# design.net
KiCad netlist of a schematic drawn in EasyEDA Pro
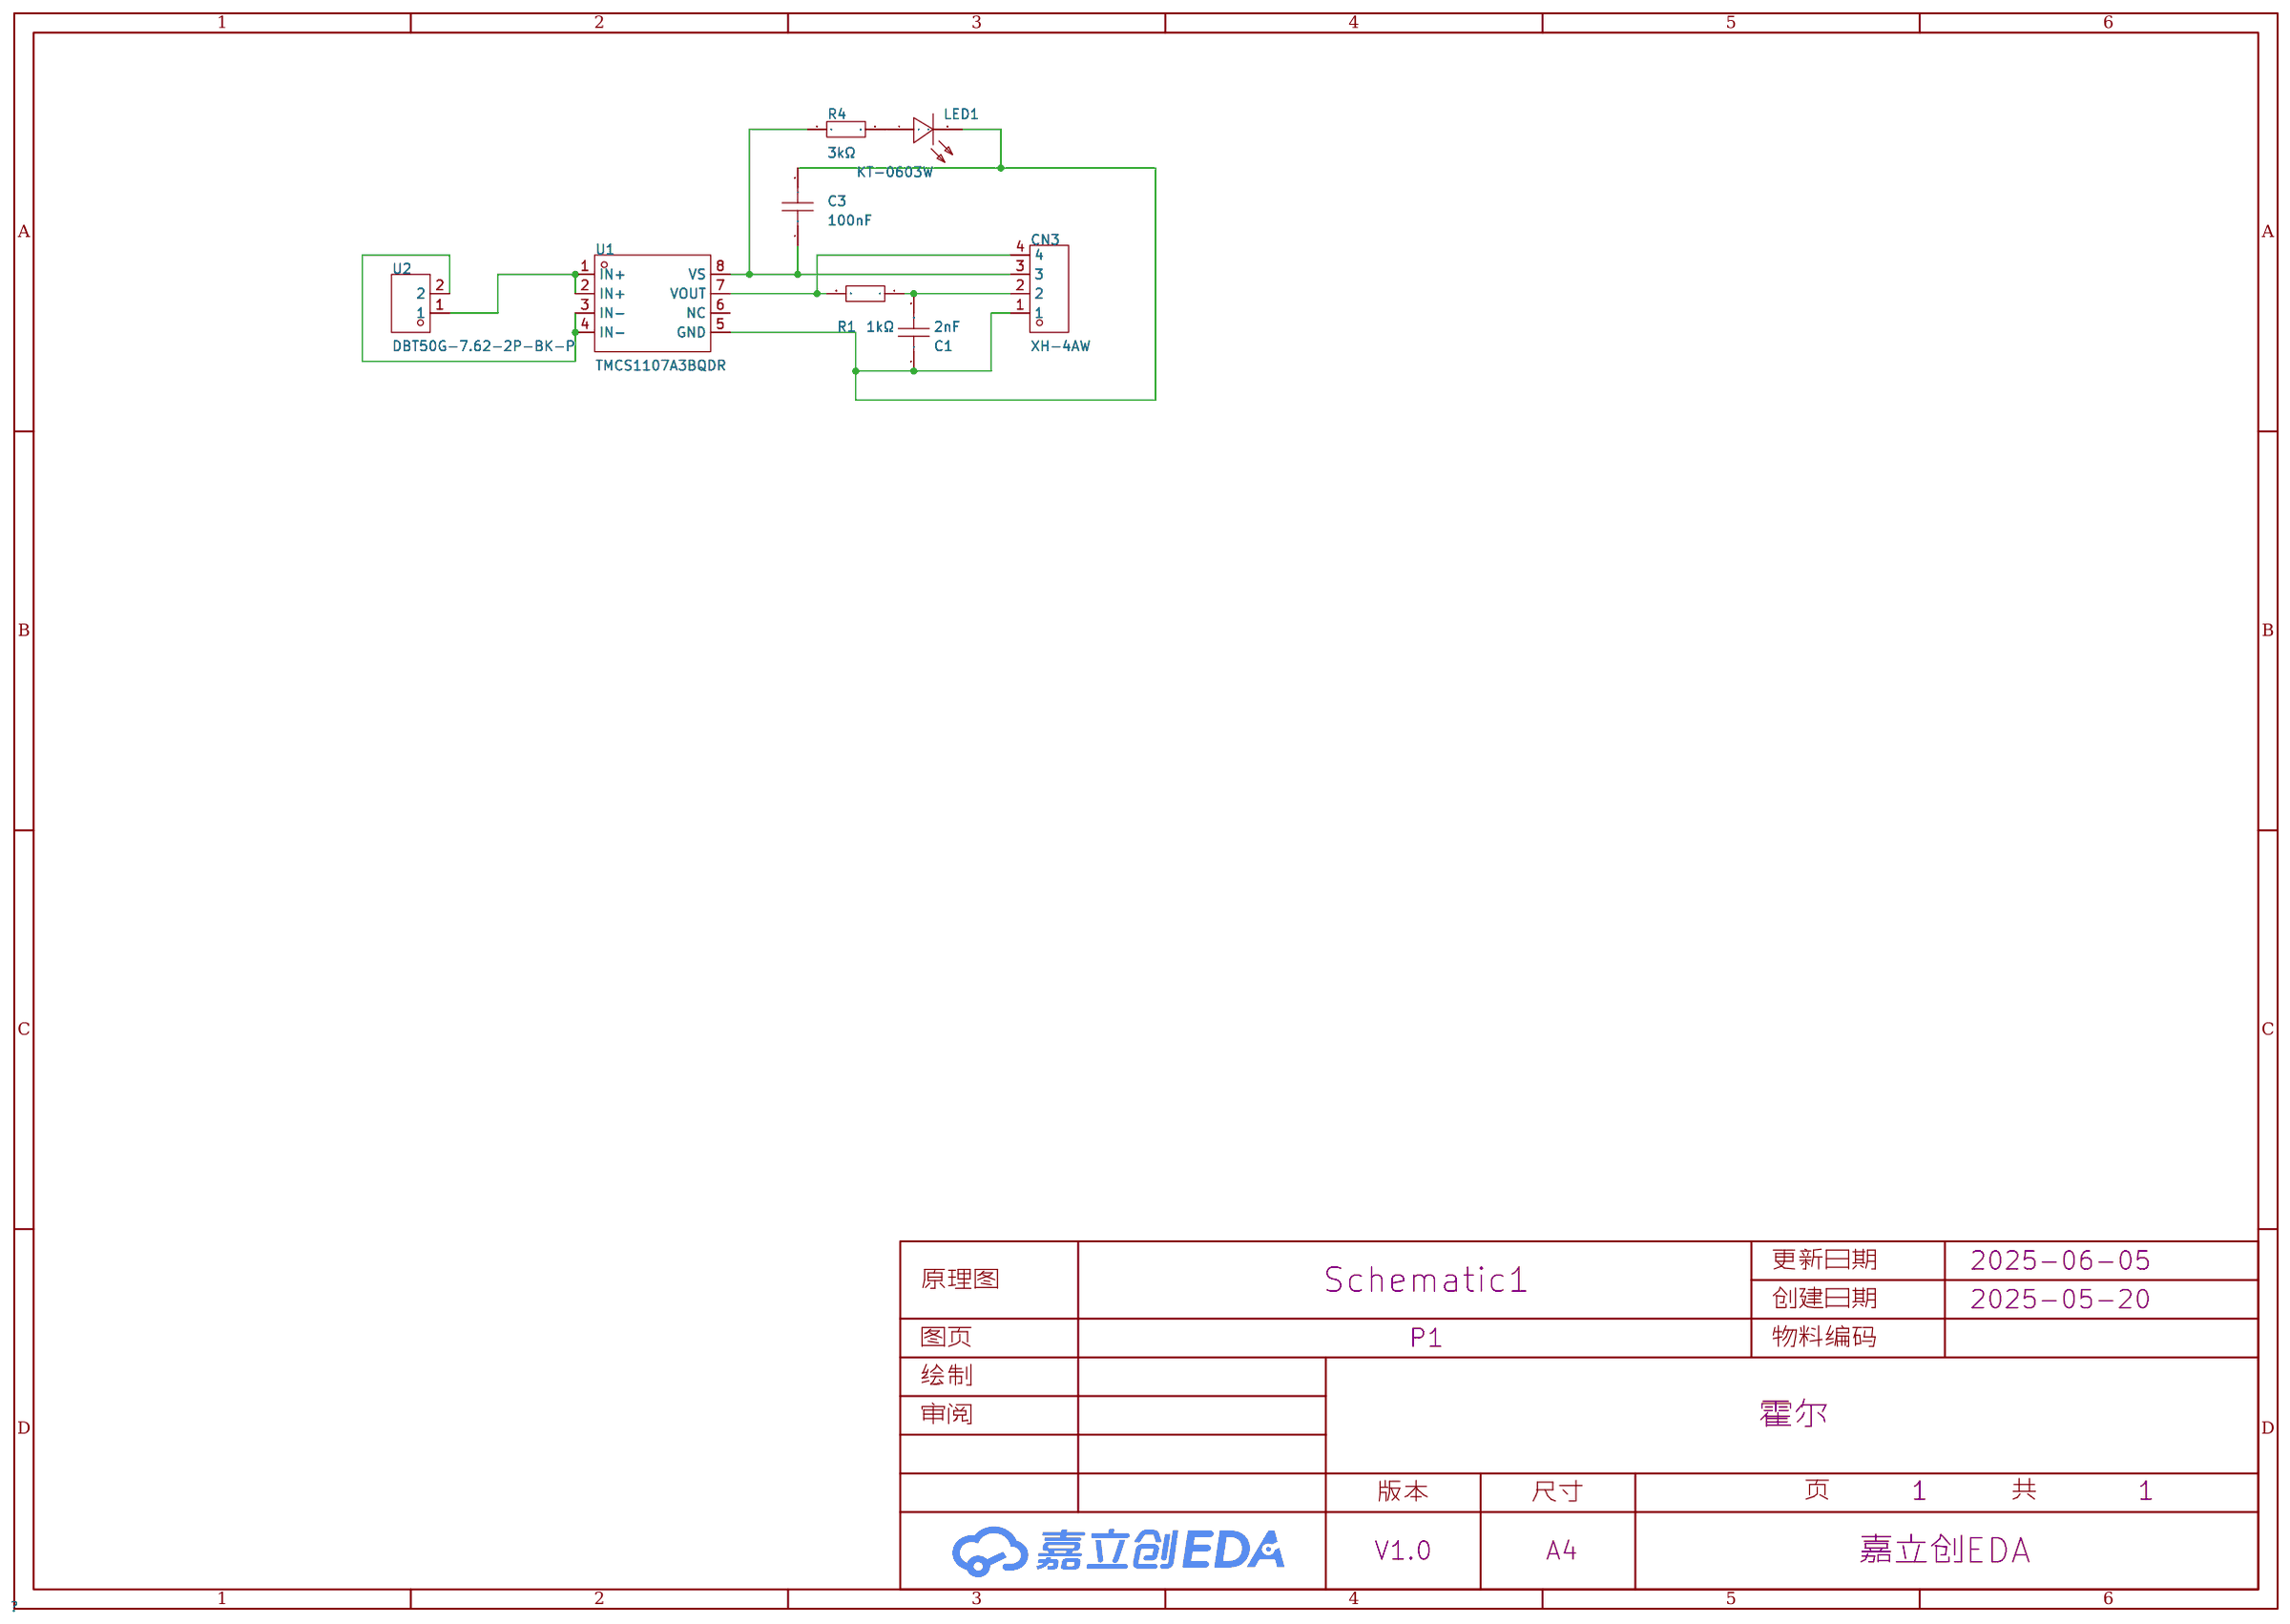
[diagram p0: schematic sheet]

(export (version "E")
  (design (tool "Eeschema 10.0.6"))
  (components
    (comp (ref "C1")
      (value "2nF")
      (footprint "easyedapro:C0603")
      (description "容值:2nF;精度:±10%;额定电压:50V;材质(温度系数):X7R;")
      (fields
        (field (name "Manufacturer Part") "CC0603KRX7R9BB202")
        (field (name "Manufacturer") "YAGEO(国巨)")
      )
      (libsource (lib "easyedapro") (part "CC0603KRX7R9BB202"))
    )
    (comp (ref "C3")
      (value "100nF")
      (footprint "easyedapro:C0603")
      (description "容值:100nF;精度:±10%;额定电压:25V;温度系数:X7R;")
      (fields
        (field (name "Manufacturer Part") "CC0603KPX7R8BB104")
        (field (name "Manufacturer") "YAGEO(国巨)")
      )
      (libsource (lib "easyedapro") (part "CC0603KPX7R8BB104"))
    )
    (comp (ref "CN3")
      (value "XH-4AW")
      (footprint "easyedapro:CONN-TH_XH-4AW")
      (fields (field (name "Manufacturer") "HCTL(华灿天禄)"))
      (libsource (lib "easyedapro") (part "XH-4AW_C2908613"))
    )
    (comp (ref "LED1")
      (value "KT-0603W")
      (footprint "easyedapro:LED0603-R-RD_WHITE")
      (description "发光颜色:白色;")
      (fields (field (name "Manufacturer") "KENTO"))
      (libsource (lib "easyedapro") (part "0603White light_C2290"))
    )
    (comp (ref "R1")
      (value "1kΩ")
      (footprint "easyedapro:R0603")
      (description "电阻类型:厚膜电阻;阻值:1kΩ;精度:±1%;功率:100mW;最大工作电压:75V;温度系数:±100ppm/°C;")
      (fields
        (field (name "Manufacturer Part") "0603WAF1001T5E")
        (field (name "Manufacturer") "UNI-ROYAL(厚声)")
      )
      (libsource (lib "easyedapro") (part "0603WAF1001T5E"))
    )
    (comp (ref "R4")
      (value "3kΩ")
      (footprint "easyedapro:R0603")
      (description "电阻类型:薄膜电阻;阻值:3kΩ;精度:±1%;功率:100mW;最大工作电压:75V;温度系数:±25ppm/°C;")
      (fields (field (name "Manufacturer Part") "ARG03FTC3001") (field (name "Manufacturer") "Viking(光颉)"))
      (libsource (lib "easyedapro") (part "ARG03FTC3001"))
    )
    (comp (ref "U1")
      (value "TMCS1107A3BQDR")
      (footprint "easyedapro:SOIC-8_L4.9-W3.9-P1.27-LS6.0-BL")
      (description "灵敏度:200mV/A;")
      (fields (field (name "Manufacturer") "TI(德州仪器)"))
      (libsource (lib "easyedapro") (part "TMCS1107A3BQDR"))
    )
    (comp (ref "U2")
      (value "DBT50G-7.62-2P-BK-P")
      (footprint "easyedapro:CONN-TH_2P-P7.62_L15.2-W16.7-EX4.2")
      (fields (field (name "Manufacturer") "DORABO(地博电气)"))
      (libsource (lib "easyedapro") (part "DBT50G-7.62-2P"))
    )
  )
  (nets
    (net (code "1") (name "Net-(C1-Pad2)") (class "Default")
      (node (ref "C1") (pin "2") (pinfunction "2_2") (pintype "unspecified"))
      (node (ref "CN3") (pin "2") (pinfunction "2_2") (pintype "unspecified"))
      (node (ref "R1") (pin "1") (pinfunction "1_1") (pintype "input"))
    )
    (net (code "2") (name "Net-(LED1-A)") (class "Default")
      (node (ref "LED1") (pin "1") (pinfunction "A_1") (pintype "unspecified"))
      (node (ref "R4") (pin "2") (pinfunction "2_2") (pintype "unspecified"))
    )
    (net (code "3") (name "Net-(LED1-K)") (class "Default")
      (node (ref "C1") (pin "1") (pinfunction "1_1") (pintype "unspecified"))
      (node (ref "C3") (pin "2") (pinfunction "2_2") (pintype "unspecified"))
      (node (ref "CN3") (pin "1") (pinfunction "1_1") (pintype "unspecified"))
      (node (ref "LED1") (pin "2") (pinfunction "K_2") (pintype "unspecified"))
      (node (ref "U1") (pin "5") (pinfunction "GND_5") (pintype "unspecified"))
    )
    (net (code "4") (name "Net-(U1-IN+-Pad1)") (class "Default")
      (node (ref "U1") (pin "1") (pinfunction "IN+_1") (pintype "unspecified"))
      (node (ref "U1") (pin "2") (pinfunction "IN+_2") (pintype "unspecified"))
      (node (ref "U2") (pin "1") (pinfunction "1_1") (pintype "unspecified"))
    )
    (net (code "5") (name "Net-(U1-IN--Pad3)") (class "Default")
      (node (ref "U1") (pin "3") (pinfunction "IN-_3") (pintype "unspecified"))
      (node (ref "U1") (pin "4") (pinfunction "IN-_4") (pintype "unspecified"))
      (node (ref "U2") (pin "2") (pinfunction "2_2") (pintype "unspecified"))
    )
    (net (code "6") (name "Net-(U1-VOUT)") (class "Default")
      (node (ref "CN3") (pin "4") (pinfunction "4_4") (pintype "unspecified"))
      (node (ref "R1") (pin "2") (pinfunction "2_2") (pintype "input"))
      (node (ref "U1") (pin "7") (pinfunction "VOUT_7") (pintype "unspecified"))
    )
    (net (code "7") (name "Net-(U1-VS)") (class "Default")
      (node (ref "C3") (pin "1") (pinfunction "1_1") (pintype "unspecified"))
      (node (ref "CN3") (pin "3") (pinfunction "3_3") (pintype "unspecified"))
      (node (ref "R4") (pin "1") (pinfunction "1_1") (pintype "unspecified"))
      (node (ref "U1") (pin "8") (pinfunction "VS_8") (pintype "unspecified"))
    )
    (net (code "8") (name "unconnected-(U1-NC-Pad6)") (class "Default")
      (node (ref "U1") (pin "6") (pinfunction "NC_6") (pintype "unspecified"))
    )
  )
)
